# USBtoTTL.net
KiCad netlist of a schematic drawn in Altium Designer
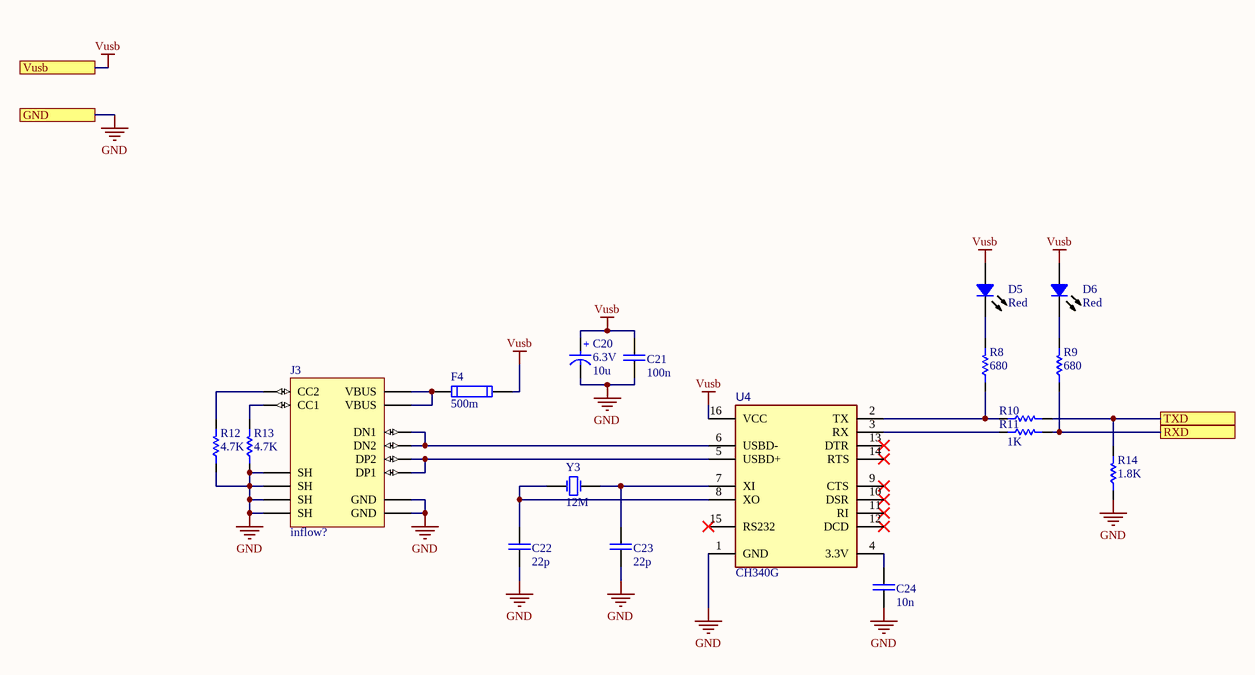
[diagram p0: USBtoTTL.SchDoc]

(export (version "E")
  (design (tool "Eeschema 10.0.6"))
  (components
    (comp (ref "C20")
      (value "10u")
      (footprint "SMT_C_Tantalum_A")
      (description "Tantalum Capacitor,TAJ Series-SMD")
      (fields (field (name "RATING") "6.3V") (field (name "VALIDATION") "Valid"))
      (libsource (lib "aKaReZa") (part "Cap_Tantalum"))
    )
    (comp (ref "C21")
      (value "100n")
      (footprint "CAP 0805/2012")
      (description "Bipolar ceramic capacitor SMD")
      (fields (field (name "VALIDATION") "Valid"))
      (libsource (lib "aKaReZa") (part "Cap_Multi_SMD_100nF_0805"))
    )
    (comp (ref "C22")
      (value "22p")
      (footprint "CAP 0805/2012")
      (description "Bipolar ceramic capacitor SMD")
      (fields (field (name "VALIDATION") "Valid"))
      (libsource (lib "aKaReZa") (part "Cap_Multi_SMD_0805"))
    )
    (comp (ref "C23")
      (value "22p")
      (footprint "CAP 0805/2012")
      (description "Bipolar ceramic capacitor SMD")
      (fields (field (name "VALIDATION") "Valid"))
      (libsource (lib "aKaReZa") (part "Cap_Multi_SMD_0805"))
    )
    (comp (ref "C24")
      (value "10n")
      (footprint "CAP 0805/2012")
      (description "Bipolar ceramic capacitor SMD")
      (fields (field (name "VALIDATION") "Valid"))
      (libsource (lib "aKaReZa") (part "Cap_Multi_SMD_0805"))
    )
    (comp (ref "D5")
      (value "Red")
      (footprint "LED 0805/2012 RED")
      (description "LED")
      (fields (field (name "VALIDATION") "Valid"))
      (libsource (lib "aKaReZa") (part "Semi_LED_SMD"))
    )
    (comp (ref "D6")
      (value "Red")
      (footprint "LED 0805/2012 RED")
      (description "LED")
      (fields (field (name "VALIDATION") "Valid"))
      (libsource (lib "aKaReZa") (part "Semi_LED_SMD"))
    )
    (comp (ref "F4")
      (value "500m")
      (footprint "1206_F")
      (description "Short circiut  protection")
      (fields (field (name "VALIDATION") "Valid"))
      (libsource (lib "aKaReZa") (part "Other_Elec_Fuse_SMD"))
    )
    (comp (ref "J3")
      (value "12b")
      (footprint "HRO_TYPE-C-31-M-12 - Extended")
      (description "USB C Female Connector")
      (fields (field (name "INFLOW") "inflow?") (field (name "VALIDATION") "Valid"))
      (libsource (lib "aKaReZa") (part "Con_USB_C"))
    )
    (comp (ref "R8")
      (value "680")
      (footprint "RES 0805 (2012X06L)")
      (description "Resistor")
      (fields (field (name "VALIDATION") "Valid"))
      (libsource (lib "aKaReZa") (part "Res_SMD_0805"))
    )
    (comp (ref "R9")
      (value "680")
      (footprint "RES 0805 (2012X06L)")
      (description "Resistor")
      (fields (field (name "VALIDATION") "Valid"))
      (libsource (lib "aKaReZa") (part "Res_SMD_0805"))
    )
    (comp (ref "R10")
      (value "1K")
      (footprint "RES 0805 (2012X06L)")
      (description "Resistor")
      (fields (field (name "VALIDATION") "Valid"))
      (libsource (lib "aKaReZa") (part "Res_SMD_0805"))
    )
    (comp (ref "R11")
      (value "1K")
      (footprint "RES 0805 (2012X06L)")
      (description "Resistor")
      (fields (field (name "VALIDATION") "Valid"))
      (libsource (lib "aKaReZa") (part "Res_SMD_0805"))
    )
    (comp (ref "R12")
      (value "4.7K")
      (footprint "RES 0805 (2012X06L)")
      (description "Resistor")
      (fields (field (name "VALIDATION") "Valid"))
      (libsource (lib "aKaReZa") (part "Res_SMD_0805"))
    )
    (comp (ref "R13")
      (value "4.7K")
      (footprint "RES 0805 (2012X06L)")
      (description "Resistor")
      (fields (field (name "VALIDATION") "Valid"))
      (libsource (lib "aKaReZa") (part "Res_SMD_0805"))
    )
    (comp (ref "R14")
      (value "1.8K")
      (footprint "RES 0805 (2012X06L)")
      (description "Resistor")
      (fields (field (name "VALIDATION") "Valid"))
      (libsource (lib "aKaReZa") (part "Res_SMD_0805"))
    )
    (comp (ref "U4")
      (value "CH340G")
      (footprint "SO16_M")
      (description "TTL To USB Chip")
      (fields (field (name "VALIDATION") "Valid"))
      (libsource (lib "aKaReZa") (part "IC_Converter_CH340G"))
    )
    (comp (ref "Y3")
      (value "12M")
      (footprint "Crystal SMD")
      (description "Crystal Oscillator")
      (fields (field (name "VALIDATION") "Valid"))
      (libsource (lib "aKaReZa") (part "Other_Elec_Xtal_SMD"))
    )
  )
  (nets
    (net (code "1") (name "/RXD") (class "Default")
      (node (ref "R11") (pin "2") (pinfunction "2_2") (pintype "passive"))
      (node (ref "R9") (pin "1") (pinfunction "1_1") (pintype "passive"))
    )
    (net (code "2") (name "/TXD") (class "Default")
      (node (ref "R10") (pin "2") (pinfunction "2_2") (pintype "passive"))
      (node (ref "R14") (pin "2") (pinfunction "2_2") (pintype "passive"))
    )
    (net (code "3") (name "GND") (class "Default")
      (node (ref "C20") (pin "2") (pinfunction "-_2") (pintype "passive"))
      (node (ref "C21") (pin "2") (pinfunction "2_2") (pintype "passive"))
      (node (ref "C22") (pin "2") (pinfunction "2_2") (pintype "passive"))
      (node (ref "C23") (pin "2") (pinfunction "2_2") (pintype "passive"))
      (node (ref "C24") (pin "2") (pinfunction "2_2") (pintype "passive"))
      (node (ref "J3") (pin "A1_B12") (pinfunction "GND_A1_B12") (pintype "power_in"))
      (node (ref "J3") (pin "B1_A12") (pinfunction "GND_B1_A12") (pintype "power_in"))
      (node (ref "J3") (pin "S1") (pinfunction "SH_S1") (pintype "passive"))
      (node (ref "J3") (pin "S2") (pinfunction "SH_S2") (pintype "passive"))
      (node (ref "J3") (pin "S3") (pinfunction "SH_S3") (pintype "passive"))
      (node (ref "J3") (pin "S4") (pinfunction "SH_S4") (pintype "passive"))
      (node (ref "R12") (pin "1") (pinfunction "1_1") (pintype "passive"))
      (node (ref "R13") (pin "1") (pinfunction "1_1") (pintype "passive"))
      (node (ref "R14") (pin "1") (pinfunction "1_1") (pintype "passive"))
      (node (ref "U4") (pin "1") (pinfunction "GND_1") (pintype "passive"))
    )
    (net (code "4") (name "Net-(D5-Pad2)") (class "Default")
      (node (ref "D5") (pin "2") (pinfunction "2_2") (pintype "passive"))
      (node (ref "R8") (pin "2") (pinfunction "2_2") (pintype "passive"))
    )
    (net (code "5") (name "Net-(D6-Pad2)") (class "Default")
      (node (ref "D6") (pin "2") (pinfunction "2_2") (pintype "passive"))
      (node (ref "R9") (pin "2") (pinfunction "2_2") (pintype "passive"))
    )
    (net (code "6") (name "Net-(F4-Pad1)") (class "Default")
      (node (ref "F4") (pin "1") (pinfunction "1_1") (pintype "passive"))
      (node (ref "J3") (pin "A4_B9") (pinfunction "VBUS_A4_B9") (pintype "power_in"))
      (node (ref "J3") (pin "B4_A9") (pinfunction "VBUS_B4_A9") (pintype "power_in"))
    )
    (net (code "7") (name "Net-(J3-CC1)") (class "Default")
      (node (ref "J3") (pin "A5") (pinfunction "CC1_A5") (pintype "bidirectional"))
      (node (ref "R13") (pin "2") (pinfunction "2_2") (pintype "passive"))
    )
    (net (code "8") (name "Net-(J3-CC2)") (class "Default")
      (node (ref "J3") (pin "B5") (pinfunction "CC2_B5") (pintype "bidirectional"))
      (node (ref "R12") (pin "2") (pinfunction "2_2") (pintype "passive"))
    )
    (net (code "9") (name "Net-(J3-DN1)") (class "Default")
      (node (ref "J3") (pin "A7") (pinfunction "DN1_A7") (pintype "bidirectional"))
      (node (ref "J3") (pin "B7") (pinfunction "DN2_B7") (pintype "bidirectional"))
      (node (ref "U4") (pin "6") (pinfunction "USBD-_6") (pintype "passive"))
    )
    (net (code "10") (name "Net-(J3-DP1)") (class "Default")
      (node (ref "J3") (pin "A6") (pinfunction "DP1_A6") (pintype "bidirectional"))
      (node (ref "J3") (pin "B6") (pinfunction "DP2_B6") (pintype "bidirectional"))
      (node (ref "U4") (pin "5") (pinfunction "USBD+_5") (pintype "passive"))
    )
    (net (code "11") (name "Net-(U4-3.3V)") (class "Default")
      (node (ref "C24") (pin "1") (pinfunction "1_1") (pintype "passive"))
      (node (ref "U4") (pin "4") (pinfunction "3.3V_4") (pintype "passive"))
    )
    (net (code "12") (name "Net-(U4-RX)") (class "Default")
      (node (ref "R11") (pin "1") (pinfunction "1_1") (pintype "passive"))
      (node (ref "U4") (pin "3") (pinfunction "RX_3") (pintype "passive"))
    )
    (net (code "13") (name "Net-(U4-TX)") (class "Default")
      (node (ref "R10") (pin "1") (pinfunction "1_1") (pintype "passive"))
      (node (ref "R8") (pin "1") (pinfunction "1_1") (pintype "passive"))
      (node (ref "U4") (pin "2") (pinfunction "TX_2") (pintype "passive"))
    )
    (net (code "14") (name "Net-(U4-XI)") (class "Default")
      (node (ref "C23") (pin "1") (pinfunction "1_1") (pintype "passive"))
      (node (ref "U4") (pin "7") (pinfunction "XI_7") (pintype "passive"))
      (node (ref "Y3") (pin "2") (pinfunction "OSC2_2") (pintype "passive"))
    )
    (net (code "15") (name "Net-(U4-XO)") (class "Default")
      (node (ref "C22") (pin "1") (pinfunction "1_1") (pintype "passive"))
      (node (ref "U4") (pin "8") (pinfunction "XO_8") (pintype "passive"))
      (node (ref "Y3") (pin "1") (pinfunction "OSC1_1") (pintype "passive"))
    )
    (net (code "16") (name "Vusb") (class "Default")
      (node (ref "C20") (pin "1") (pinfunction "+_1") (pintype "passive"))
      (node (ref "C21") (pin "1") (pinfunction "1_1") (pintype "passive"))
      (node (ref "D5") (pin "1") (pinfunction "1_1") (pintype "passive"))
      (node (ref "D6") (pin "1") (pinfunction "1_1") (pintype "passive"))
      (node (ref "F4") (pin "2") (pinfunction "2_2") (pintype "passive"))
      (node (ref "U4") (pin "16") (pinfunction "VCC_16") (pintype "passive"))
    )
    (net (code "17") (name "unconnected-(U4-CTS-Pad9)") (class "Default")
      (node (ref "U4") (pin "9") (pinfunction "CTS_9") (pintype "passive+no_connect"))
    )
    (net (code "18") (name "unconnected-(U4-DCD-Pad12)") (class "Default")
      (node (ref "U4") (pin "12") (pinfunction "DCD_12") (pintype "passive+no_connect"))
    )
    (net (code "19") (name "unconnected-(U4-DSR-Pad10)") (class "Default")
      (node (ref "U4") (pin "10") (pinfunction "DSR_10") (pintype "passive+no_connect"))
    )
    (net (code "20") (name "unconnected-(U4-DTR-Pad13)") (class "Default")
      (node (ref "U4") (pin "13") (pinfunction "DTR_13") (pintype "passive+no_connect"))
    )
    (net (code "21") (name "unconnected-(U4-RI-Pad11)") (class "Default")
      (node (ref "U4") (pin "11") (pinfunction "RI_11") (pintype "passive+no_connect"))
    )
    (net (code "22") (name "unconnected-(U4-RS232-Pad15)") (class "Default")
      (node (ref "U4") (pin "15") (pinfunction "RS232_15") (pintype "passive+no_connect"))
    )
    (net (code "23") (name "unconnected-(U4-RTS-Pad14)") (class "Default")
      (node (ref "U4") (pin "14") (pinfunction "RTS_14") (pintype "passive+no_connect"))
    )
  )
)
